# communication.net
KiCad netlist of a schematic drawn in Altium Designer
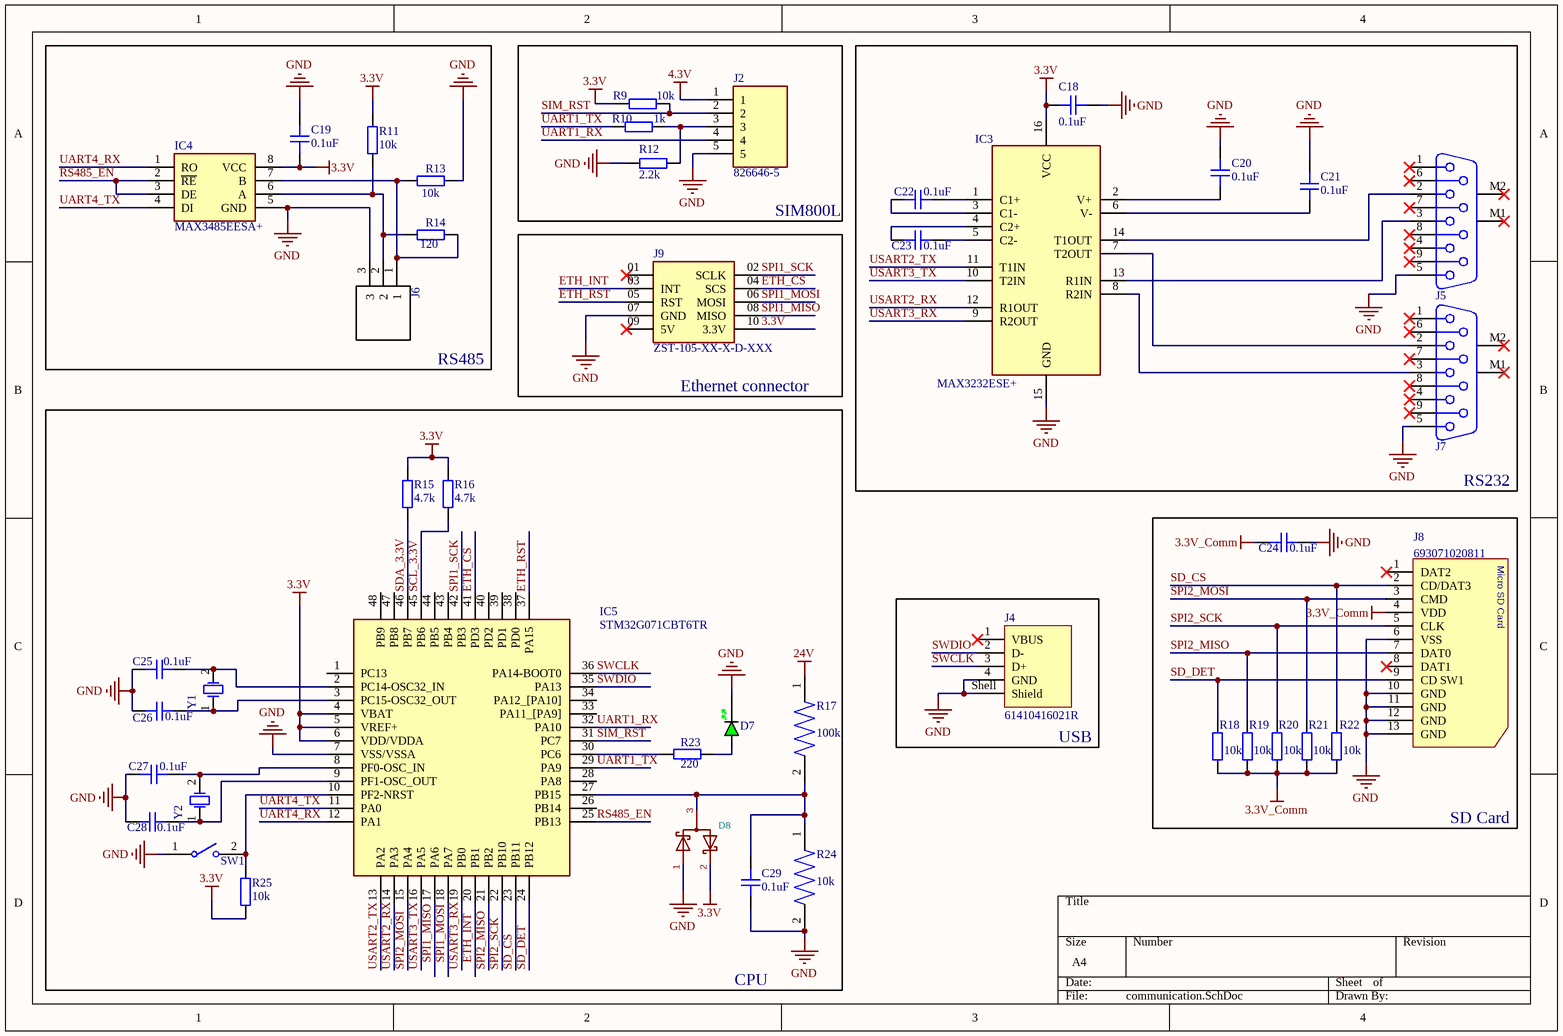
[diagram p0: communication.SchDoc]

(export (version "E")
  (design (tool "Eeschema 10.0.6"))
  (components
    (comp (ref "C18")
      (value "0.1uF")
      (footprint "CAP_0805")
      (description "Capacitor SMD 0805")
      (libsource (lib "Schematic-Lib-PhilsLab") (part "CAP_0805"))
    )
    (comp (ref "C19")
      (value "0.1uF")
      (footprint "CAP_0805")
      (description "Capacitor SMD 0805")
      (libsource (lib "Schematic-Lib-PhilsLab") (part "CAP_0805"))
    )
    (comp (ref "C20")
      (value "0.1uF")
      (footprint "CAP_0805")
      (description "Capacitor SMD 0805")
      (libsource (lib "Schematic-Lib-PhilsLab") (part "CAP_0805"))
    )
    (comp (ref "C21")
      (value "0.1uF")
      (footprint "CAP_0805")
      (description "Capacitor SMD 0805")
      (libsource (lib "Schematic-Lib-PhilsLab") (part "CAP_0805"))
    )
    (comp (ref "C22")
      (value "0.1uF")
      (footprint "CAP_0805")
      (description "Capacitor SMD 0805")
      (libsource (lib "Schematic-Lib-PhilsLab") (part "CAP_0805"))
    )
    (comp (ref "C23")
      (value "0.1uF")
      (footprint "CAP_0805")
      (description "Capacitor SMD 0805")
      (libsource (lib "Schematic-Lib-PhilsLab") (part "CAP_0805"))
    )
    (comp (ref "C24")
      (value "0.1uF")
      (footprint "CAP_0805")
      (description "Capacitor SMD 0805")
      (libsource (lib "Schematic-Lib-PhilsLab") (part "CAP_0805"))
    )
    (comp (ref "C25")
      (value "0.1uF")
      (footprint "CAP_0805")
      (description "Capacitor SMD 0805")
      (libsource (lib "Schematic-Lib-PhilsLab") (part "CAP_0805"))
    )
    (comp (ref "C26")
      (value "0.1uF")
      (footprint "CAP_0805")
      (description "Capacitor SMD 0805")
      (libsource (lib "Schematic-Lib-PhilsLab") (part "CAP_0805"))
    )
    (comp (ref "C27")
      (value "0.1uF")
      (footprint "CAP_0805")
      (description "Capacitor SMD 0805")
      (libsource (lib "Schematic-Lib-PhilsLab") (part "CAP_0805"))
    )
    (comp (ref "C28")
      (value "0.1uF")
      (footprint "CAP_0805")
      (description "Capacitor SMD 0805")
      (libsource (lib "Schematic-Lib-PhilsLab") (part "CAP_0805"))
    )
    (comp (ref "C29")
      (value "0.1uF")
      (footprint "CAP_0805")
      (description "Capacitor SMD 0805")
      (libsource (lib "Schematic-Lib-PhilsLab") (part "CAP_0805"))
    )
    (comp (ref "D7")
      (value "GREEN")
      (footprint "LED_0805_GREEN")
      (description "LED 0805 GREEN SMD")
      (libsource (lib "Schematic-Lib-PhilsLab") (part "LED_0805_GREEN"))
    )
    (comp (ref "D8")
      (value "Schottky-Dual-Diode_Series")
      (footprint "SOT-23")
      (libsource (lib "schottky-dual-diode_series") (part "Schottky-Dual-Diode_Series"))
    )
    (comp (ref "IC3")
      (value "MAX3232ESE+")
      (footprint "SOIC127P600X175-16N")
      (description "Integrated Circuit")
      (fields (field (name "MOUSER PART NUMBER") "700-MAX3232ESE"))
      (libsource (lib "1") (part "MAX3232ESE+"))
    )
    (comp (ref "IC4")
      (value "MAX3485EESA+")
      (footprint "SOIC127P600X175-8N")
      (description "Integrated Circuit")
      (fields (field (name "MOUSER PART NUMBER") "700-MAX3485EESA"))
      (libsource (lib "*") (part "MAX3485EESA+"))
    )
    (comp (ref "IC5")
      (value "STM32G071CBT6TR")
      (footprint "QFP50P900X900X160-48N")
      (description "Integrated Circuit")
      (fields (field (name "MOUSER PART NUMBER") "511-STM32G071CBT6TR"))
      (libsource (lib "1") (part "STM32G071CBT6TR"))
    )
    (comp (ref "J2")
      (value "826646-5")
      (footprint "TE_826646-5")
      (description "Board-To-Board Connector, Through Hole, Header, 5, 2.54 mm, Gold Plated Contacts")
      (fields (field (name "MF") "TE Connectivity"))
      (libsource (lib "826646-5") (part "826646-5"))
    )
    (comp (ref "J4")
      (value "61410416021R")
      (footprint "61410416021R")
      (description "WR-COM USB 2.0 Type A Horizontal THR")
      (fields (field (name "MANUFACTURER") "Wurth Elektronik"))
      (libsource (lib "WR-USB") (part "61410416021R"))
    )
    (comp (ref "J5")
      (value "Female, Straight, 9p")
      (footprint "210611003")
      (description "WE-D-SUB Filter Connector, THT, Straight, Female, 9p")
      (fields
        (field (name "MANUFACTURER PART NUMBER") "210611003")
        (field (name "MANUFACTURER") "Wurth Elektronik")
      )
      (libsource (lib "RS232 DB9") (part "210611003"))
    )
    (comp (ref "J6")
      (value "TBP04R1-500-03BE")
      (footprint "*CUI_TBP04R1-500-03BE")
      (libsource (lib "TBP04R1-500-03BE") (part "TBP04R1-500-03BE"))
    )
    (comp (ref "J7")
      (value "Female, Straight, 9p")
      (footprint "210611003")
      (description "WE-D-SUB Filter Connector, THT, Straight, Female, 9p")
      (fields
        (field (name "MANUFACTURER PART NUMBER") "210611003")
        (field (name "MANUFACTURER") "Wurth Elektronik")
      )
      (libsource (lib "RS232 DB9") (part "210611003"))
    )
    (comp (ref "J8")
      (value "693071020811")
      (footprint "693071020811")
      (description "WR-CRD SD Card Connector Push & Push Socket, 8 pins")
      (fields (field (name "MANUFACTURER") "Wurth Elektronik"))
      (libsource (lib "WR-CRD") (part "693071020811"))
    )
    (comp (ref "J9")
      (value "ZST-105-XX-X-D-XXX")
      (footprint "SAMTEC_ZST-105-XX-X-D-XXX")
      (fields (field (name "MF") "Samtec") (field (name "MP") "ZST10501FD450"))
      (libsource (lib "ZST-105-XX-X-D-XXX") (part "ZST-105-XX-X-D-XXX"))
    )
    (comp (ref "R9")
      (value "10k")
      (footprint "RES_1206")
      (description "Resistor SMD 1206")
      (libsource (lib "Schematic-Lib-PhilsLab") (part "RES_1206"))
    )
    (comp (ref "R10")
      (value "1k")
      (footprint "RES_1206")
      (description "Resistor SMD 1206")
      (libsource (lib "Schematic-Lib-PhilsLab") (part "RES_1206"))
    )
    (comp (ref "R11")
      (value "10k")
      (footprint "RES_1206")
      (description "Resistor SMD 1206")
      (libsource (lib "Schematic-Lib-PhilsLab") (part "RES_1206"))
    )
    (comp (ref "R12")
      (value "2.2k")
      (footprint "RES_1206")
      (description "Resistor SMD 1206")
      (libsource (lib "Schematic-Lib-PhilsLab") (part "RES_1206"))
    )
    (comp (ref "R13")
      (value "10k")
      (footprint "RES_1206")
      (description "Resistor SMD 1206")
      (libsource (lib "Schematic-Lib-PhilsLab") (part "RES_1206"))
    )
    (comp (ref "R14")
      (value "120")
      (footprint "RES_1206")
      (description "Resistor SMD 1206")
      (libsource (lib "Schematic-Lib-PhilsLab") (part "RES_1206"))
    )
    (comp (ref "R15")
      (value "4.7k")
      (footprint "RES_1206")
      (description "Resistor SMD 1206")
      (libsource (lib "Schematic-Lib-PhilsLab") (part "RES_1206"))
    )
    (comp (ref "R16")
      (value "4.7k")
      (footprint "RES_1206")
      (description "Resistor SMD 1206")
      (libsource (lib "Schematic-Lib-PhilsLab") (part "RES_1206"))
    )
    (comp (ref "R17")
      (value "100k")
      (footprint "RESAD700W45L350D185")
      (description "1 MOhms Â±5% 1W, 1/4W Through Hole Resistor Axial - Carbon Film")
      (fields (field (name "MF") "TE Connectivity") (field (name "MP") "3-1623927-1"))
      (libsource (lib "TH res") (part "3-1623927-1"))
    )
    (comp (ref "R18")
      (value "10k")
      (footprint "RES_1206")
      (description "Resistor SMD 1206")
      (libsource (lib "Schematic-Lib-PhilsLab") (part "RES_1206"))
    )
    (comp (ref "R19")
      (value "10k")
      (footprint "RES_1206")
      (description "Resistor SMD 1206")
      (libsource (lib "Schematic-Lib-PhilsLab") (part "RES_1206"))
    )
    (comp (ref "R20")
      (value "10k")
      (footprint "RES_1206")
      (description "Resistor SMD 1206")
      (libsource (lib "Schematic-Lib-PhilsLab") (part "RES_1206"))
    )
    (comp (ref "R21")
      (value "10k")
      (footprint "RES_1206")
      (description "Resistor SMD 1206")
      (libsource (lib "Schematic-Lib-PhilsLab") (part "RES_1206"))
    )
    (comp (ref "R22")
      (value "10k")
      (footprint "RES_1206")
      (description "Resistor SMD 1206")
      (libsource (lib "Schematic-Lib-PhilsLab") (part "RES_1206"))
    )
    (comp (ref "R23")
      (value "220")
      (footprint "RES_1206")
      (description "Resistor SMD 1206")
      (libsource (lib "Schematic-Lib-PhilsLab") (part "RES_1206"))
    )
    (comp (ref "R24")
      (value "10k")
      (footprint "RESAD700W45L350D185")
      (description "1 MOhms Â±5% 1W, 1/4W Through Hole Resistor Axial - Carbon Film")
      (fields (field (name "MF") "TE Connectivity") (field (name "MP") "3-1623927-1"))
      (libsource (lib "TH res") (part "3-1623927-1"))
    )
    (comp (ref "R25")
      (value "10k")
      (footprint "RES_1206")
      (description "Resistor SMD 1206")
      (libsource (lib "Schematic-Lib-PhilsLab") (part "RES_1206"))
    )
    (comp (ref "SW1")
      (value "434121043816")
      (footprint "434121043816")
      (description "WS-TASV SMT Tact Switch, 6mm x 3.5mm x 4.3mm, SPST-NO, 160gf, 12V, 50mA")
      (fields (field (name "MANUFACTURER") "Wurth Elektronik"))
      (libsource (lib "WS-TASV") (part "434121043816"))
    )
    (comp (ref "Y1")
      (value "32.768kHz")
      (footprint "WE-XTAL_WATCH_D3H8.2")
      (description "WE-XTAL Watch Crystal, WATCH, 32.768kHz, +/-20ppm")
      (fields
        (field (name "MANUFACTURER PART NUMBER") "830002995B")
        (field (name "MANUFACTURER") "Wurth Elektronik")
      )
      (libsource (lib "WE-XTAL") (part "830002995B"))
    )
    (comp (ref "Y2")
      (value "10MHz")
      (footprint "WE-XTAL_HC49/4H")
      (description "WE-XTAL Quartz Crystal, HC49/4H, 10MHz, +/-30ppm")
      (fields
        (field (name "MANUFACTURER PART NUMBER") "830003169B")
        (field (name "MANUFACTURER") "Wurth Elektronik")
      )
      (libsource (lib "WE-XTAL") (part "830003169B"))
    )
  )
  (nets
    (net (code "1") (name "/ETH_CS") (class "Default")
      (node (ref "IC5") (pin "41") (pinfunction "PD3_41") (pintype "passive"))
      (node (ref "J9") (pin "04") (pinfunction "SCS_04") (pintype "passive"))
    )
    (net (code "2") (name "/ETH_INT") (class "Default")
      (node (ref "IC5") (pin "20") (pinfunction "PB1_20") (pintype "passive"))
      (node (ref "J9") (pin "03") (pinfunction "INT_03") (pintype "passive"))
    )
    (net (code "3") (name "/ETH_RST") (class "Default")
      (node (ref "IC5") (pin "37") (pinfunction "PA15_37") (pintype "passive"))
      (node (ref "J9") (pin "05") (pinfunction "RST_05") (pintype "passive"))
    )
    (net (code "4") (name "/RS485_EN") (class "Default")
      (node (ref "IC4") (pin "2") (pinfunction "~{RE}_2") (pintype "passive"))
      (node (ref "IC4") (pin "3") (pinfunction "DE_3") (pintype "passive"))
      (node (ref "IC5") (pin "25") (pinfunction "PB13_25") (pintype "passive"))
    )
    (net (code "5") (name "/SCL_3.3V") (class "Default")
      (node (ref "IC5") (pin "45") (pinfunction "PB6_45") (pintype "passive"))
      (node (ref "R16") (pin "2") (pinfunction "2_2") (pintype "passive"))
    )
    (net (code "6") (name "/SDA_3.3V") (class "Default")
      (node (ref "IC5") (pin "46") (pinfunction "PB7_46") (pintype "passive"))
      (node (ref "R15") (pin "2") (pinfunction "2_2") (pintype "passive"))
    )
    (net (code "7") (name "/SD_CS") (class "Default")
      (node (ref "IC5") (pin "23") (pinfunction "PB11_23") (pintype "passive"))
      (node (ref "J8") (pin "2") (pinfunction "CD/DAT3_2") (pintype "passive"))
      (node (ref "R22") (pin "1") (pinfunction "1_1") (pintype "passive"))
    )
    (net (code "8") (name "/SD_DET") (class "Default")
      (node (ref "IC5") (pin "24") (pinfunction "PB12_24") (pintype "passive"))
      (node (ref "J8") (pin "9") (pinfunction "CD_SW1_9") (pintype "passive"))
      (node (ref "R18") (pin "1") (pinfunction "1_1") (pintype "passive"))
    )
    (net (code "9") (name "/SIM_RST") (class "Default")
      (node (ref "IC5") (pin "31") (pinfunction "PC7_31") (pintype "passive"))
      (node (ref "J2") (pin "2") (pinfunction "2_2") (pintype "passive"))
      (node (ref "R9") (pin "1") (pinfunction "1_1") (pintype "passive"))
    )
    (net (code "10") (name "/SPI1_MISO") (class "Default")
      (node (ref "IC5") (pin "17") (pinfunction "PA6_17") (pintype "passive"))
      (node (ref "J9") (pin "08") (pinfunction "MISO_08") (pintype "passive"))
    )
    (net (code "11") (name "/SPI1_MOSI") (class "Default")
      (node (ref "IC5") (pin "18") (pinfunction "PA7_18") (pintype "passive"))
      (node (ref "J9") (pin "06") (pinfunction "MOSI_06") (pintype "passive"))
    )
    (net (code "12") (name "/SPI1_SCK") (class "Default")
      (node (ref "IC5") (pin "42") (pinfunction "PB3_42") (pintype "passive"))
      (node (ref "J9") (pin "02") (pinfunction "SCLK_02") (pintype "passive"))
    )
    (net (code "13") (name "/SPI2_MISO") (class "Default")
      (node (ref "IC5") (pin "21") (pinfunction "PB2_21") (pintype "passive"))
      (node (ref "J8") (pin "7") (pinfunction "DAT0_7") (pintype "passive"))
      (node (ref "R19") (pin "1") (pinfunction "1_1") (pintype "passive"))
    )
    (net (code "14") (name "/SPI2_MOSI") (class "Default")
      (node (ref "IC5") (pin "15") (pinfunction "PA4_15") (pintype "passive"))
      (node (ref "J8") (pin "3") (pinfunction "CMD_3") (pintype "passive"))
      (node (ref "R21") (pin "1") (pinfunction "1_1") (pintype "passive"))
    )
    (net (code "15") (name "/SPI2_SCK") (class "Default")
      (node (ref "IC5") (pin "22") (pinfunction "PB10_22") (pintype "passive"))
      (node (ref "J8") (pin "5") (pinfunction "CLK_5") (pintype "passive"))
      (node (ref "R20") (pin "1") (pinfunction "1_1") (pintype "passive"))
    )
    (net (code "16") (name "/SWCLK") (class "Default")
      (node (ref "IC5") (pin "36") (pinfunction "PA14-BOOT0_36") (pintype "passive"))
      (node (ref "J4") (pin "3") (pinfunction "D+_3") (pintype "passive"))
    )
    (net (code "17") (name "/SWDIO") (class "Default")
      (node (ref "IC5") (pin "35") (pinfunction "PA13_35") (pintype "passive"))
      (node (ref "J4") (pin "2") (pinfunction "D-_2") (pintype "passive"))
    )
    (net (code "18") (name "/UART1_RX") (class "Default")
      (node (ref "IC5") (pin "32") (pinfunction "PA10_32") (pintype "passive"))
      (node (ref "J2") (pin "4") (pinfunction "4_4") (pintype "passive"))
    )
    (net (code "19") (name "/UART1_TX") (class "Default")
      (node (ref "IC5") (pin "29") (pinfunction "PA9_29") (pintype "passive"))
      (node (ref "R10") (pin "1") (pinfunction "1_1") (pintype "passive"))
    )
    (net (code "20") (name "/UART4_RX") (class "Default")
      (node (ref "IC4") (pin "1") (pinfunction "RO_1") (pintype "passive"))
      (node (ref "IC5") (pin "12") (pinfunction "PA1_12") (pintype "passive"))
    )
    (net (code "21") (name "/UART4_TX") (class "Default")
      (node (ref "IC4") (pin "4") (pinfunction "DI_4") (pintype "passive"))
      (node (ref "IC5") (pin "11") (pinfunction "PA0_11") (pintype "passive"))
    )
    (net (code "22") (name "/USART2_RX") (class "Default")
      (node (ref "IC3") (pin "12") (pinfunction "R1OUT_12") (pintype "passive"))
      (node (ref "IC5") (pin "14") (pinfunction "PA3_14") (pintype "passive"))
    )
    (net (code "23") (name "/USART2_TX") (class "Default")
      (node (ref "IC3") (pin "11") (pinfunction "T1IN_11") (pintype "passive"))
      (node (ref "IC5") (pin "13") (pinfunction "PA2_13") (pintype "passive"))
    )
    (net (code "24") (name "/USART3_RX") (class "Default")
      (node (ref "IC3") (pin "9") (pinfunction "R2OUT_9") (pintype "passive"))
      (node (ref "IC5") (pin "19") (pinfunction "PB0_19") (pintype "passive"))
    )
    (net (code "25") (name "/USART3_TX") (class "Default")
      (node (ref "IC3") (pin "10") (pinfunction "T2IN_10") (pintype "passive"))
      (node (ref "IC5") (pin "16") (pinfunction "PA5_16") (pintype "passive"))
    )
    (net (code "26") (name "3.3V") (class "Default")
      (node (ref "C18") (pin "2") (pinfunction "2_2") (pintype "passive"))
      (node (ref "C19") (pin "1") (pinfunction "1_1") (pintype "passive"))
      (node (ref "D8") (pin "2") (pinfunction "C_2") (pintype "passive"))
      (node (ref "IC3") (pin "16") (pinfunction "VCC_16") (pintype "passive"))
      (node (ref "IC4") (pin "8") (pinfunction "VCC_8") (pintype "passive"))
      (node (ref "IC5") (pin "4") (pinfunction "VBAT_4") (pintype "passive"))
      (node (ref "IC5") (pin "5") (pinfunction "VREF+_5") (pintype "passive"))
      (node (ref "IC5") (pin "6") (pinfunction "VDD/VDDA_6") (pintype "passive"))
      (node (ref "J9") (pin "10") (pinfunction "3.3V_10") (pintype "passive"))
      (node (ref "R11") (pin "1") (pinfunction "1_1") (pintype "passive"))
      (node (ref "R15") (pin "1") (pinfunction "1_1") (pintype "passive"))
      (node (ref "R16") (pin "1") (pinfunction "1_1") (pintype "passive"))
      (node (ref "R25") (pin "2") (pinfunction "2_2") (pintype "passive"))
      (node (ref "R9") (pin "2") (pinfunction "2_2") (pintype "passive"))
    )
    (net (code "27") (name "3.3V_Comm") (class "Default")
      (node (ref "C24") (pin "2") (pinfunction "2_2") (pintype "passive"))
      (node (ref "J8") (pin "4") (pinfunction "VDD_4") (pintype "passive"))
      (node (ref "R18") (pin "2") (pinfunction "2_2") (pintype "passive"))
      (node (ref "R19") (pin "2") (pinfunction "2_2") (pintype "passive"))
      (node (ref "R20") (pin "2") (pinfunction "2_2") (pintype "passive"))
      (node (ref "R21") (pin "2") (pinfunction "2_2") (pintype "passive"))
      (node (ref "R22") (pin "2") (pinfunction "2_2") (pintype "passive"))
    )
    (net (code "28") (name "4.3V") (class "Default")
      (node (ref "J2") (pin "1") (pinfunction "1_1") (pintype "passive"))
    )
    (net (code "29") (name "24V") (class "Default")
      (node (ref "R17") (pin "1") (pinfunction "1_1") (pintype "passive"))
    )
    (net (code "30") (name "GND") (class "Default")
      (node (ref "C18") (pin "1") (pinfunction "1_1") (pintype "passive"))
      (node (ref "C19") (pin "2") (pinfunction "2_2") (pintype "passive"))
      (node (ref "C20") (pin "2") (pinfunction "2_2") (pintype "passive"))
      (node (ref "C21") (pin "1") (pinfunction "1_1") (pintype "passive"))
      (node (ref "C24") (pin "1") (pinfunction "1_1") (pintype "passive"))
      (node (ref "C25") (pin "2") (pinfunction "2_2") (pintype "passive"))
      (node (ref "C26") (pin "2") (pinfunction "2_2") (pintype "passive"))
      (node (ref "C27") (pin "2") (pinfunction "2_2") (pintype "passive"))
      (node (ref "C28") (pin "2") (pinfunction "2_2") (pintype "passive"))
      (node (ref "C29") (pin "1") (pinfunction "1_1") (pintype "passive"))
      (node (ref "D7") (pin "K") (pinfunction "K_K") (pintype "passive"))
      (node (ref "D8") (pin "1") (pinfunction "A_1") (pintype "passive"))
      (node (ref "IC3") (pin "15") (pinfunction "GND_15") (pintype "passive"))
      (node (ref "IC4") (pin "5") (pinfunction "GND_5") (pintype "passive"))
      (node (ref "IC5") (pin "7") (pinfunction "VSS/VSSA_7") (pintype "passive"))
      (node (ref "J2") (pin "5") (pinfunction "5_5") (pintype "passive"))
      (node (ref "J4") (pin "4") (pinfunction "GND_4") (pintype "passive"))
      (node (ref "J4") (pin "Shell") (pinfunction "Shield_Shell") (pintype "passive"))
      (node (ref "J5") (pin "5") (pinfunction "5_5") (pintype "passive"))
      (node (ref "J6") (pin "3") (pinfunction "3_3") (pintype "passive"))
      (node (ref "J7") (pin "5") (pinfunction "5_5") (pintype "passive"))
      (node (ref "J8") (pin "10") (pinfunction "GND_10") (pintype "passive"))
      (node (ref "J8") (pin "11") (pinfunction "GND_11") (pintype "passive"))
      (node (ref "J8") (pin "12") (pinfunction "GND_12") (pintype "passive"))
      (node (ref "J8") (pin "13") (pinfunction "GND_13") (pintype "passive"))
      (node (ref "J8") (pin "6") (pinfunction "VSS_6") (pintype "passive"))
      (node (ref "J9") (pin "07") (pinfunction "GND_07") (pintype "passive"))
      (node (ref "R12") (pin "1") (pinfunction "1_1") (pintype "passive"))
      (node (ref "R13") (pin "1") (pinfunction "1_1") (pintype "passive"))
      (node (ref "R24") (pin "2") (pinfunction "2_2") (pintype "passive"))
      (node (ref "SW1") (pin "1") (pinfunction "1_1") (pintype "passive"))
    )
    (net (code "31") (name "Net-(D7-PadA)") (class "Default")
      (node (ref "D7") (pin "A") (pinfunction "A_A") (pintype "passive"))
      (node (ref "R23") (pin "1") (pinfunction "1_1") (pintype "passive"))
    )
    (net (code "32") (name "Net-(IC3-C1+)") (class "Default")
      (node (ref "C22") (pin "2") (pinfunction "2_2") (pintype "passive"))
      (node (ref "IC3") (pin "1") (pinfunction "C1+_1") (pintype "passive"))
    )
    (net (code "33") (name "Net-(IC3-C1-)") (class "Default")
      (node (ref "C22") (pin "1") (pinfunction "1_1") (pintype "passive"))
      (node (ref "IC3") (pin "3") (pinfunction "C1-_3") (pintype "passive"))
    )
    (net (code "34") (name "Net-(IC3-C2+)") (class "Default")
      (node (ref "C23") (pin "2") (pinfunction "2_2") (pintype "passive"))
      (node (ref "IC3") (pin "4") (pinfunction "C2+_4") (pintype "passive"))
    )
    (net (code "35") (name "Net-(IC3-C2-)") (class "Default")
      (node (ref "C23") (pin "1") (pinfunction "1_1") (pintype "passive"))
      (node (ref "IC3") (pin "5") (pinfunction "C2-_5") (pintype "passive"))
    )
    (net (code "36") (name "Net-(IC3-R1IN)") (class "Default")
      (node (ref "IC3") (pin "13") (pinfunction "R1IN_13") (pintype "passive"))
      (node (ref "J5") (pin "3") (pinfunction "3_3") (pintype "passive"))
    )
    (net (code "37") (name "Net-(IC3-R2IN)") (class "Default")
      (node (ref "IC3") (pin "8") (pinfunction "R2IN_8") (pintype "passive"))
      (node (ref "J7") (pin "3") (pinfunction "3_3") (pintype "passive"))
    )
    (net (code "38") (name "Net-(IC3-T1OUT)") (class "Default")
      (node (ref "IC3") (pin "14") (pinfunction "T1OUT_14") (pintype "passive"))
      (node (ref "J5") (pin "2") (pinfunction "2_2") (pintype "passive"))
    )
    (net (code "39") (name "Net-(IC3-T2OUT)") (class "Default")
      (node (ref "IC3") (pin "7") (pinfunction "T2OUT_7") (pintype "passive"))
      (node (ref "J7") (pin "2") (pinfunction "2_2") (pintype "passive"))
    )
    (net (code "40") (name "Net-(IC3-V+)") (class "Default")
      (node (ref "C20") (pin "1") (pinfunction "1_1") (pintype "passive"))
      (node (ref "IC3") (pin "2") (pinfunction "V+_2") (pintype "passive"))
    )
    (net (code "41") (name "Net-(IC3-V-)") (class "Default")
      (node (ref "C21") (pin "2") (pinfunction "2_2") (pintype "passive"))
      (node (ref "IC3") (pin "6") (pinfunction "V-_6") (pintype "passive"))
    )
    (net (code "42") (name "Net-(IC4-A)") (class "Default")
      (node (ref "IC4") (pin "6") (pinfunction "A_6") (pintype "passive"))
      (node (ref "J6") (pin "2") (pinfunction "2_2") (pintype "passive"))
      (node (ref "R11") (pin "2") (pinfunction "2_2") (pintype "passive"))
      (node (ref "R14") (pin "2") (pinfunction "2_2") (pintype "passive"))
    )
    (net (code "43") (name "Net-(IC4-B)") (class "Default")
      (node (ref "IC4") (pin "7") (pinfunction "B_7") (pintype "passive"))
      (node (ref "J6") (pin "1") (pinfunction "1_1") (pintype "passive"))
      (node (ref "R13") (pin "2") (pinfunction "2_2") (pintype "passive"))
      (node (ref "R14") (pin "1") (pinfunction "1_1") (pintype "passive"))
    )
    (net (code "44") (name "Net-(IC5-PB15)") (class "Default")
      (node (ref "C29") (pin "2") (pinfunction "2_2") (pintype "passive"))
      (node (ref "D8") (pin "3") (pinfunction "3_3") (pintype "passive"))
      (node (ref "IC5") (pin "27") (pinfunction "PB15_27") (pintype "passive"))
      (node (ref "R17") (pin "2") (pinfunction "2_2") (pintype "passive"))
      (node (ref "R24") (pin "1") (pinfunction "1_1") (pintype "passive"))
    )
    (net (code "45") (name "Net-(IC5-PC6)") (class "Default")
      (node (ref "IC5") (pin "30") (pinfunction "PC6_30") (pintype "passive"))
      (node (ref "R23") (pin "2") (pinfunction "2_2") (pintype "passive"))
    )
    (net (code "46") (name "Net-(IC5-PC14-OSC32_IN)") (class "Default")
      (node (ref "C25") (pin "1") (pinfunction "1_1") (pintype "passive"))
      (node (ref "IC5") (pin "2") (pinfunction "PC14-OSC32_IN_2") (pintype "passive"))
      (node (ref "Y1") (pin "2") (pinfunction "OSC2_2") (pintype "passive"))
    )
    (net (code "47") (name "Net-(IC5-PC15-OSC32_OUT)") (class "Default")
      (node (ref "C26") (pin "1") (pinfunction "1_1") (pintype "passive"))
      (node (ref "IC5") (pin "3") (pinfunction "PC15-OSC32_OUT_3") (pintype "passive"))
      (node (ref "Y1") (pin "1") (pinfunction "OSC1_1") (pintype "passive"))
    )
    (net (code "48") (name "Net-(IC5-PF0-OSC_IN)") (class "Default")
      (node (ref "C27") (pin "1") (pinfunction "1_1") (pintype "passive"))
      (node (ref "IC5") (pin "8") (pinfunction "PF0-OSC_IN_8") (pintype "passive"))
      (node (ref "Y2") (pin "2") (pinfunction "OSC2_2") (pintype "passive"))
    )
    (net (code "49") (name "Net-(IC5-PF1-OSC_OUT)") (class "Default")
      (node (ref "C28") (pin "1") (pinfunction "1_1") (pintype "passive"))
      (node (ref "IC5") (pin "9") (pinfunction "PF1-OSC_OUT_9") (pintype "passive"))
      (node (ref "Y2") (pin "1") (pinfunction "OSC1_1") (pintype "passive"))
    )
    (net (code "50") (name "Net-(IC5-PF2-NRST)") (class "Default")
      (node (ref "IC5") (pin "10") (pinfunction "PF2-NRST_10") (pintype "passive"))
      (node (ref "R25") (pin "1") (pinfunction "1_1") (pintype "passive"))
      (node (ref "SW1") (pin "2") (pinfunction "2_2") (pintype "passive"))
    )
    (net (code "51") (name "Net-(J2-Pad3)") (class "Default")
      (node (ref "J2") (pin "3") (pinfunction "3_3") (pintype "passive"))
      (node (ref "R10") (pin "2") (pinfunction "2_2") (pintype "passive"))
      (node (ref "R12") (pin "2") (pinfunction "2_2") (pintype "passive"))
    )
    (net (code "52") (name "unconnected-(IC5-PA8-Pad28)") (class "Default")
      (node (ref "IC5") (pin "28") (pinfunction "PA8_28") (pintype "passive"))
    )
    (net (code "53") (name "unconnected-(IC5-PA11_[PA9]-Pad33)") (class "Default")
      (node (ref "IC5") (pin "33") (pinfunction "PA11_[PA9]_33") (pintype "passive"))
    )
    (net (code "54") (name "unconnected-(IC5-PA12_[PA10]-Pad34)") (class "Default")
      (node (ref "IC5") (pin "34") (pinfunction "PA12_[PA10]_34") (pintype "passive"))
    )
    (net (code "55") (name "unconnected-(IC5-PB4-Pad43)") (class "Default")
      (node (ref "IC5") (pin "43") (pinfunction "PB4_43") (pintype "passive"))
    )
    (net (code "56") (name "unconnected-(IC5-PB5-Pad44)") (class "Default")
      (node (ref "IC5") (pin "44") (pinfunction "PB5_44") (pintype "passive"))
    )
    (net (code "57") (name "unconnected-(IC5-PB8-Pad47)") (class "Default")
      (node (ref "IC5") (pin "47") (pinfunction "PB8_47") (pintype "passive"))
    )
    (net (code "58") (name "unconnected-(IC5-PB9-Pad48)") (class "Default")
      (node (ref "IC5") (pin "48") (pinfunction "PB9_48") (pintype "passive"))
    )
    (net (code "59") (name "unconnected-(IC5-PB14-Pad26)") (class "Default")
      (node (ref "IC5") (pin "26") (pinfunction "PB14_26") (pintype "passive"))
    )
    (net (code "60") (name "unconnected-(IC5-PC13-Pad1)") (class "Default")
      (node (ref "IC5") (pin "1") (pinfunction "PC13_1") (pintype "passive"))
    )
    (net (code "61") (name "unconnected-(IC5-PD0-Pad38)") (class "Default")
      (node (ref "IC5") (pin "38") (pinfunction "PD0_38") (pintype "passive"))
    )
    (net (code "62") (name "unconnected-(IC5-PD1-Pad39)") (class "Default")
      (node (ref "IC5") (pin "39") (pinfunction "PD1_39") (pintype "passive"))
    )
    (net (code "63") (name "unconnected-(IC5-PD2-Pad40)") (class "Default")
      (node (ref "IC5") (pin "40") (pinfunction "PD2_40") (pintype "passive"))
    )
    (net (code "64") (name "unconnected-(J4-VBUS-Pad1)") (class "Default")
      (node (ref "J4") (pin "1") (pinfunction "VBUS_1") (pintype "passive+no_connect"))
    )
    (net (code "65") (name "unconnected-(J5-Pad1)") (class "Default")
      (node (ref "J5") (pin "1") (pinfunction "1_1") (pintype "passive+no_connect"))
    )
    (net (code "66") (name "unconnected-(J5-Pad4)") (class "Default")
      (node (ref "J5") (pin "4") (pinfunction "4_4") (pintype "passive+no_connect"))
    )
    (net (code "67") (name "unconnected-(J5-Pad6)") (class "Default")
      (node (ref "J5") (pin "6") (pinfunction "6_6") (pintype "passive+no_connect"))
    )
    (net (code "68") (name "unconnected-(J5-Pad7)") (class "Default")
      (node (ref "J5") (pin "7") (pinfunction "7_7") (pintype "passive+no_connect"))
    )
    (net (code "69") (name "unconnected-(J5-Pad8)") (class "Default")
      (node (ref "J5") (pin "8") (pinfunction "8_8") (pintype "passive+no_connect"))
    )
    (net (code "70") (name "unconnected-(J5-Pad9)") (class "Default")
      (node (ref "J5") (pin "9") (pinfunction "9_9") (pintype "passive+no_connect"))
    )
    (net (code "71") (name "unconnected-(J5-PadM1)") (class "Default")
      (node (ref "J5") (pin "M1") (pinfunction "M1_M1") (pintype "passive+no_connect"))
    )
    (net (code "72") (name "unconnected-(J5-PadM2)") (class "Default")
      (node (ref "J5") (pin "M2") (pinfunction "M2_M2") (pintype "passive+no_connect"))
    )
    (net (code "73") (name "unconnected-(J7-Pad1)") (class "Default")
      (node (ref "J7") (pin "1") (pinfunction "1_1") (pintype "passive+no_connect"))
    )
    (net (code "74") (name "unconnected-(J7-Pad4)") (class "Default")
      (node (ref "J7") (pin "4") (pinfunction "4_4") (pintype "passive+no_connect"))
    )
    (net (code "75") (name "unconnected-(J7-Pad6)") (class "Default")
      (node (ref "J7") (pin "6") (pinfunction "6_6") (pintype "passive+no_connect"))
    )
    (net (code "76") (name "unconnected-(J7-Pad7)") (class "Default")
      (node (ref "J7") (pin "7") (pinfunction "7_7") (pintype "passive+no_connect"))
    )
    (net (code "77") (name "unconnected-(J7-Pad8)") (class "Default")
      (node (ref "J7") (pin "8") (pinfunction "8_8") (pintype "passive+no_connect"))
    )
    (net (code "78") (name "unconnected-(J7-Pad9)") (class "Default")
      (node (ref "J7") (pin "9") (pinfunction "9_9") (pintype "passive+no_connect"))
    )
    (net (code "79") (name "unconnected-(J7-PadM1)") (class "Default")
      (node (ref "J7") (pin "M1") (pinfunction "M1_M1") (pintype "passive+no_connect"))
    )
    (net (code "80") (name "unconnected-(J7-PadM2)") (class "Default")
      (node (ref "J7") (pin "M2") (pinfunction "M2_M2") (pintype "passive+no_connect"))
    )
    (net (code "81") (name "unconnected-(J8-DAT1-Pad8)") (class "Default")
      (node (ref "J8") (pin "8") (pinfunction "DAT1_8") (pintype "passive+no_connect"))
    )
    (net (code "82") (name "unconnected-(J8-DAT2-Pad1)") (class "Default")
      (node (ref "J8") (pin "1") (pinfunction "DAT2_1") (pintype "passive+no_connect"))
    )
    (net (code "83") (name "unconnected-(J9-5V-Pad09)") (class "Default")
      (node (ref "J9") (pin "09") (pinfunction "5V_09") (pintype "passive+no_connect"))
    )
    (net (code "84") (name "unconnected-(J9-Pad01)") (class "Default")
      (node (ref "J9") (pin "01") (pintype "passive+no_connect"))
    )
  )
)
